# MPPT_CC_CV_Charger_B.net
KiCad netlist of a schematic drawn in Altium Designer
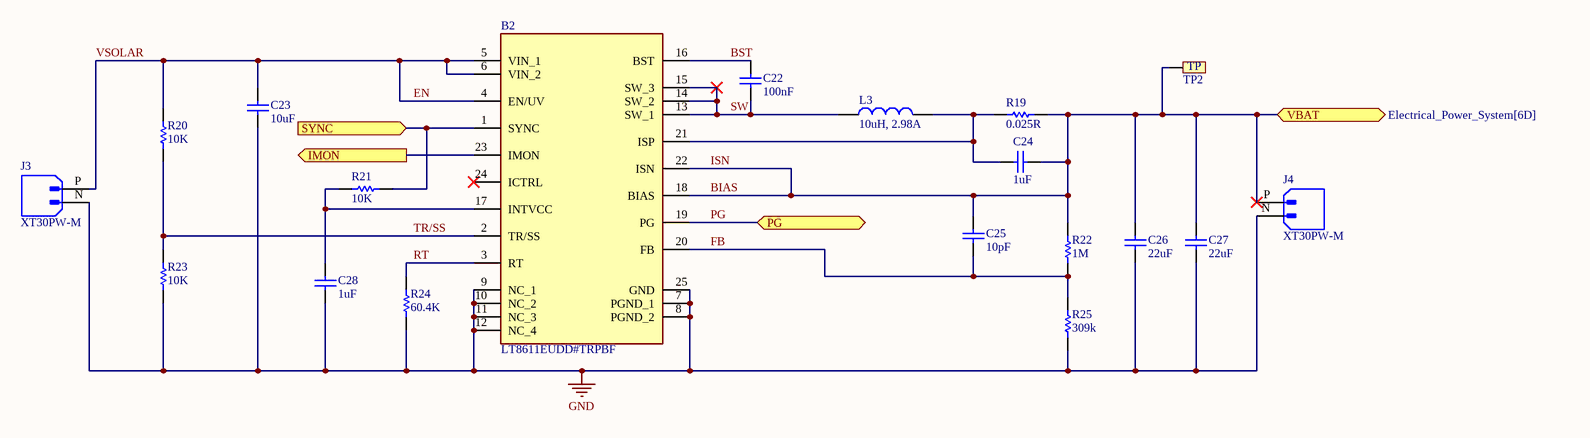
[diagram p0: MPPT_CC_CV_Charger_B.SchDoc]

(export (version "E")
  (design (tool "Eeschema 10.0.6"))
  (components
    (comp (ref "B2")
      (value "LT8611EUDD#TRPBF")
      (footprint "QFN50P300X500X80-25N-D")
      (description "42V, 2.5A Synchronous Step-Down Regulator with Current Sense and 2.5uA Quiescent Current")
      (fields (field (name "MOUSER PART NUMBER") "584-LT8611EUDD#TRPBF"))
      (libsource (lib "EPS_Board_Lib") (part "LT8611EUDD#TRPBF"))
    )
    (comp (ref "C22")
      (value "100nF")
      (footprint "CAP-SM-0603")
      (description "Capacitor")
      (fields (field (name "Comment") "Cap Non-Pol SMD"))
      (libsource (lib "PIF_Library") (part "Cap Non-Pol SMD"))
    )
    (comp (ref "C23")
      (value "10uF")
      (footprint "CAP-SM-0603")
      (description "Capacitor")
      (fields (field (name "Comment") "Cap Non-Pol SMD"))
      (libsource (lib "PIF_Library") (part "Cap Non-Pol SMD"))
    )
    (comp (ref "C24")
      (value "1uF")
      (footprint "CAP-SM-0603")
      (description "Capacitor")
      (fields (field (name "Comment") "Cap Non-Pol SMD"))
      (libsource (lib "PIF_Library") (part "Cap Non-Pol SMD"))
    )
    (comp (ref "C25")
      (value "10pF")
      (footprint "CAP-SM-0603")
      (description "Capacitor")
      (fields (field (name "Comment") "Cap Non-Pol SMD"))
      (libsource (lib "PIF_Library") (part "Cap Non-Pol SMD"))
    )
    (comp (ref "C26")
      (value "22uF")
      (footprint "CAP-SM-0603")
      (description "Capacitor")
      (fields (field (name "Comment") "Cap Non-Pol SMD"))
      (libsource (lib "PIF_Library") (part "Cap Non-Pol SMD"))
    )
    (comp (ref "C27")
      (value "22uF")
      (footprint "CAP-SM-0603")
      (description "Capacitor")
      (fields (field (name "Comment") "Cap Non-Pol SMD"))
      (libsource (lib "PIF_Library") (part "Cap Non-Pol SMD"))
    )
    (comp (ref "C28")
      (value "1uF")
      (footprint "CAP-SM-0603")
      (description "Capacitor")
      (fields (field (name "Comment") "Cap Non-Pol SMD"))
      (libsource (lib "PIF_Library") (part "Cap Non-Pol SMD"))
    )
    (comp (ref "J3")
      (value "XT30PW-M")
      (footprint "AMASS_XT30PW-M")
      (description "Socket; DC supply; XT30; male; PIN: 2; on PCBs; THT; Colour: yellow")
      (fields (field (name "MF") "AMASS"))
      (libsource (lib "") (part "XT30PW-M_1"))
    )
    (comp (ref "J4")
      (value "XT30PW-M")
      (footprint "AMASS_XT30PW-M")
      (description "Socket; DC supply; XT30; male; PIN: 2; on PCBs; THT; Colour: yellow")
      (fields (field (name "MF") "AMASS"))
      (libsource (lib "EPS_Board_Lib") (part "XT30PW-M"))
    )
    (comp (ref "L3")
      (value "10uH, 2.98A")
      (footprint "WE-PD2A_1054")
      (description "WE-PD2A SMT Power Inductor, size 1054, 10uH, 2.98A")
      (fields
        (field (name "MANUFACTURER PART NUMBER") "78477610")
        (field (name "MANUFACTURER") "Wurth Elektronik")
      )
      (libsource (lib "Altium_Coil_Inductor") (part "78477610"))
    )
    (comp (ref "R19")
      (value "0.025R")
      (footprint "RES-SM-0603")
      (description "Resistor")
      (fields (field (name "Comment") "RESISTOR SMD"))
      (libsource (lib "PIF_Library") (part "RESISTOR SMD"))
    )
    (comp (ref "R20")
      (value "10K")
      (footprint "RES-SM-0603")
      (description "Resistor")
      (fields (field (name "Comment") "RESISTOR SMD"))
      (libsource (lib "PIF_Library") (part "RESISTOR SMD"))
    )
    (comp (ref "R21")
      (value "10K")
      (footprint "RES-SM-0603")
      (description "Resistor")
      (fields (field (name "Comment") "RESISTOR SMD"))
      (libsource (lib "PIF_Library") (part "RESISTOR SMD"))
    )
    (comp (ref "R22")
      (value "1M")
      (footprint "RES-SM-0603")
      (description "Resistor")
      (fields (field (name "Comment") "RESISTOR SMD"))
      (libsource (lib "PIF_Library") (part "RESISTOR SMD"))
    )
    (comp (ref "R23")
      (value "10K")
      (footprint "RES-SM-0603")
      (description "Resistor")
      (fields (field (name "Comment") "RESISTOR SMD"))
      (libsource (lib "PIF_Library") (part "RESISTOR SMD"))
    )
    (comp (ref "R24")
      (value "60.4K")
      (footprint "RES-SM-0603")
      (description "Resistor")
      (fields (field (name "Comment") "RESISTOR SMD"))
      (libsource (lib "PIF_Library") (part "RESISTOR SMD"))
    )
    (comp (ref "R25")
      (value "309k")
      (footprint "RES-SM-0603")
      (description "Resistor")
      (fields (field (name "Comment") "RESISTOR SMD"))
      (libsource (lib "PIF_Library") (part "RESISTOR SMD"))
    )
    (comp (ref "TP2")
      (value "Test Point")
      (footprint "TP")
      (libsource (lib "PIF_Library") (part "Test Point"))
    )
  )
  (nets
    (net (code "1") (name "/BIAS") (class "Default")
      (node (ref "B2") (pin "18") (pinfunction "BIAS_18") (pintype "passive"))
      (node (ref "B2") (pin "22") (pinfunction "ISN_22") (pintype "passive"))
      (node (ref "C24") (pin "1") (pinfunction "1_1") (pintype "passive"))
      (node (ref "C25") (pin "2") (pinfunction "2_2") (pintype "passive"))
      (node (ref "C26") (pin "2") (pinfunction "2_2") (pintype "passive"))
      (node (ref "C27") (pin "2") (pinfunction "2_2") (pintype "passive"))
      (node (ref "J4") (pin "P") (pinfunction "P_P") (pintype "power_in"))
      (node (ref "R19") (pin "1") (pinfunction "1_1") (pintype "passive"))
      (node (ref "R22") (pin "2") (pinfunction "2_2") (pintype "passive"))
      (node (ref "TP2") (pin "TP1") (pinfunction "0_TP1") (pintype "passive"))
    )
    (net (code "2") (name "/BST") (class "Default")
      (node (ref "B2") (pin "16") (pinfunction "BST_16") (pintype "passive"))
      (node (ref "C22") (pin "2") (pinfunction "2_2") (pintype "passive"))
    )
    (net (code "3") (name "/EN") (class "Default")
      (node (ref "B2") (pin "4") (pinfunction "EN/UV_4") (pintype "passive"))
      (node (ref "B2") (pin "5") (pinfunction "VIN_1_5") (pintype "passive"))
      (node (ref "B2") (pin "6") (pinfunction "VIN_2_6") (pintype "passive"))
      (node (ref "C23") (pin "2") (pinfunction "2_2") (pintype "passive"))
      (node (ref "J3") (pin "P") (pinfunction "P_P") (pintype "power_in"))
      (node (ref "R20") (pin "2") (pinfunction "2_2") (pintype "passive"))
    )
    (net (code "4") (name "/FB") (class "Default")
      (node (ref "B2") (pin "20") (pinfunction "FB_20") (pintype "passive"))
      (node (ref "C25") (pin "1") (pinfunction "1_1") (pintype "passive"))
      (node (ref "R22") (pin "1") (pinfunction "1_1") (pintype "passive"))
      (node (ref "R25") (pin "2") (pinfunction "2_2") (pintype "passive"))
    )
    (net (code "5") (name "/IMON") (class "Default")
      (node (ref "B2") (pin "23") (pinfunction "IMON_23") (pintype "passive"))
    )
    (net (code "6") (name "/PG") (class "Default")
      (node (ref "B2") (pin "19") (pinfunction "PG_19") (pintype "passive"))
    )
    (net (code "7") (name "/RT") (class "Default")
      (node (ref "B2") (pin "3") (pinfunction "RT_3") (pintype "passive"))
      (node (ref "R24") (pin "2") (pinfunction "2_2") (pintype "passive"))
    )
    (net (code "8") (name "/SW") (class "Default")
      (node (ref "B2") (pin "13") (pinfunction "SW_1_13") (pintype "passive"))
      (node (ref "B2") (pin "14") (pinfunction "SW_2_14") (pintype "passive"))
      (node (ref "B2") (pin "15") (pinfunction "SW_3_15") (pintype "passive"))
      (node (ref "C22") (pin "1") (pinfunction "1_1") (pintype "passive"))
      (node (ref "L3") (pin "1") (pinfunction "1_1") (pintype "passive"))
    )
    (net (code "9") (name "/SYNC") (class "Default")
      (node (ref "B2") (pin "1") (pinfunction "SYNC_1") (pintype "passive"))
      (node (ref "R21") (pin "1") (pinfunction "1_1") (pintype "passive"))
    )
    (net (code "10") (name "/TR{slash}SS") (class "Default")
      (node (ref "B2") (pin "2") (pinfunction "TR/SS_2") (pintype "passive"))
      (node (ref "R20") (pin "1") (pinfunction "1_1") (pintype "passive"))
      (node (ref "R23") (pin "2") (pinfunction "2_2") (pintype "passive"))
    )
    (net (code "11") (name "GND") (class "Default")
      (node (ref "B2") (pin "10") (pinfunction "NC_2_10") (pintype "passive"))
      (node (ref "B2") (pin "11") (pinfunction "NC_3_11") (pintype "passive"))
      (node (ref "B2") (pin "12") (pinfunction "NC_4_12") (pintype "passive"))
      (node (ref "B2") (pin "25") (pinfunction "GND_25") (pintype "passive"))
      (node (ref "B2") (pin "7") (pinfunction "PGND_1_7") (pintype "passive"))
      (node (ref "B2") (pin "8") (pinfunction "PGND_2_8") (pintype "passive"))
      (node (ref "B2") (pin "9") (pinfunction "NC_1_9") (pintype "passive"))
      (node (ref "C23") (pin "1") (pinfunction "1_1") (pintype "passive"))
      (node (ref "C26") (pin "1") (pinfunction "1_1") (pintype "passive"))
      (node (ref "C27") (pin "1") (pinfunction "1_1") (pintype "passive"))
      (node (ref "C28") (pin "1") (pinfunction "1_1") (pintype "passive"))
      (node (ref "J3") (pin "N") (pinfunction "N_N") (pintype "power_in"))
      (node (ref "J4") (pin "N") (pinfunction "N_N") (pintype "power_in"))
      (node (ref "R23") (pin "1") (pinfunction "1_1") (pintype "passive"))
      (node (ref "R24") (pin "1") (pinfunction "1_1") (pintype "passive"))
      (node (ref "R25") (pin "1") (pinfunction "1_1") (pintype "passive"))
    )
    (net (code "12") (name "Net-(B2-INTVCC)") (class "Default")
      (node (ref "B2") (pin "17") (pinfunction "INTVCC_17") (pintype "passive"))
      (node (ref "C28") (pin "2") (pinfunction "2_2") (pintype "passive"))
      (node (ref "R21") (pin "2") (pinfunction "2_2") (pintype "passive"))
    )
    (net (code "13") (name "Net-(B2-ISP)") (class "Default")
      (node (ref "B2") (pin "21") (pinfunction "ISP_21") (pintype "passive"))
      (node (ref "C24") (pin "2") (pinfunction "2_2") (pintype "passive"))
      (node (ref "L3") (pin "2") (pinfunction "2_2") (pintype "passive"))
      (node (ref "R19") (pin "2") (pinfunction "2_2") (pintype "passive"))
    )
    (net (code "14") (name "unconnected-(B2-ICTRL-Pad24)") (class "Default")
      (node (ref "B2") (pin "24") (pinfunction "ICTRL_24") (pintype "passive+no_connect"))
    )
  )
)
